# SUNRISE_EasyEDA.net
KiCad netlist of a schematic drawn in EasyEDA
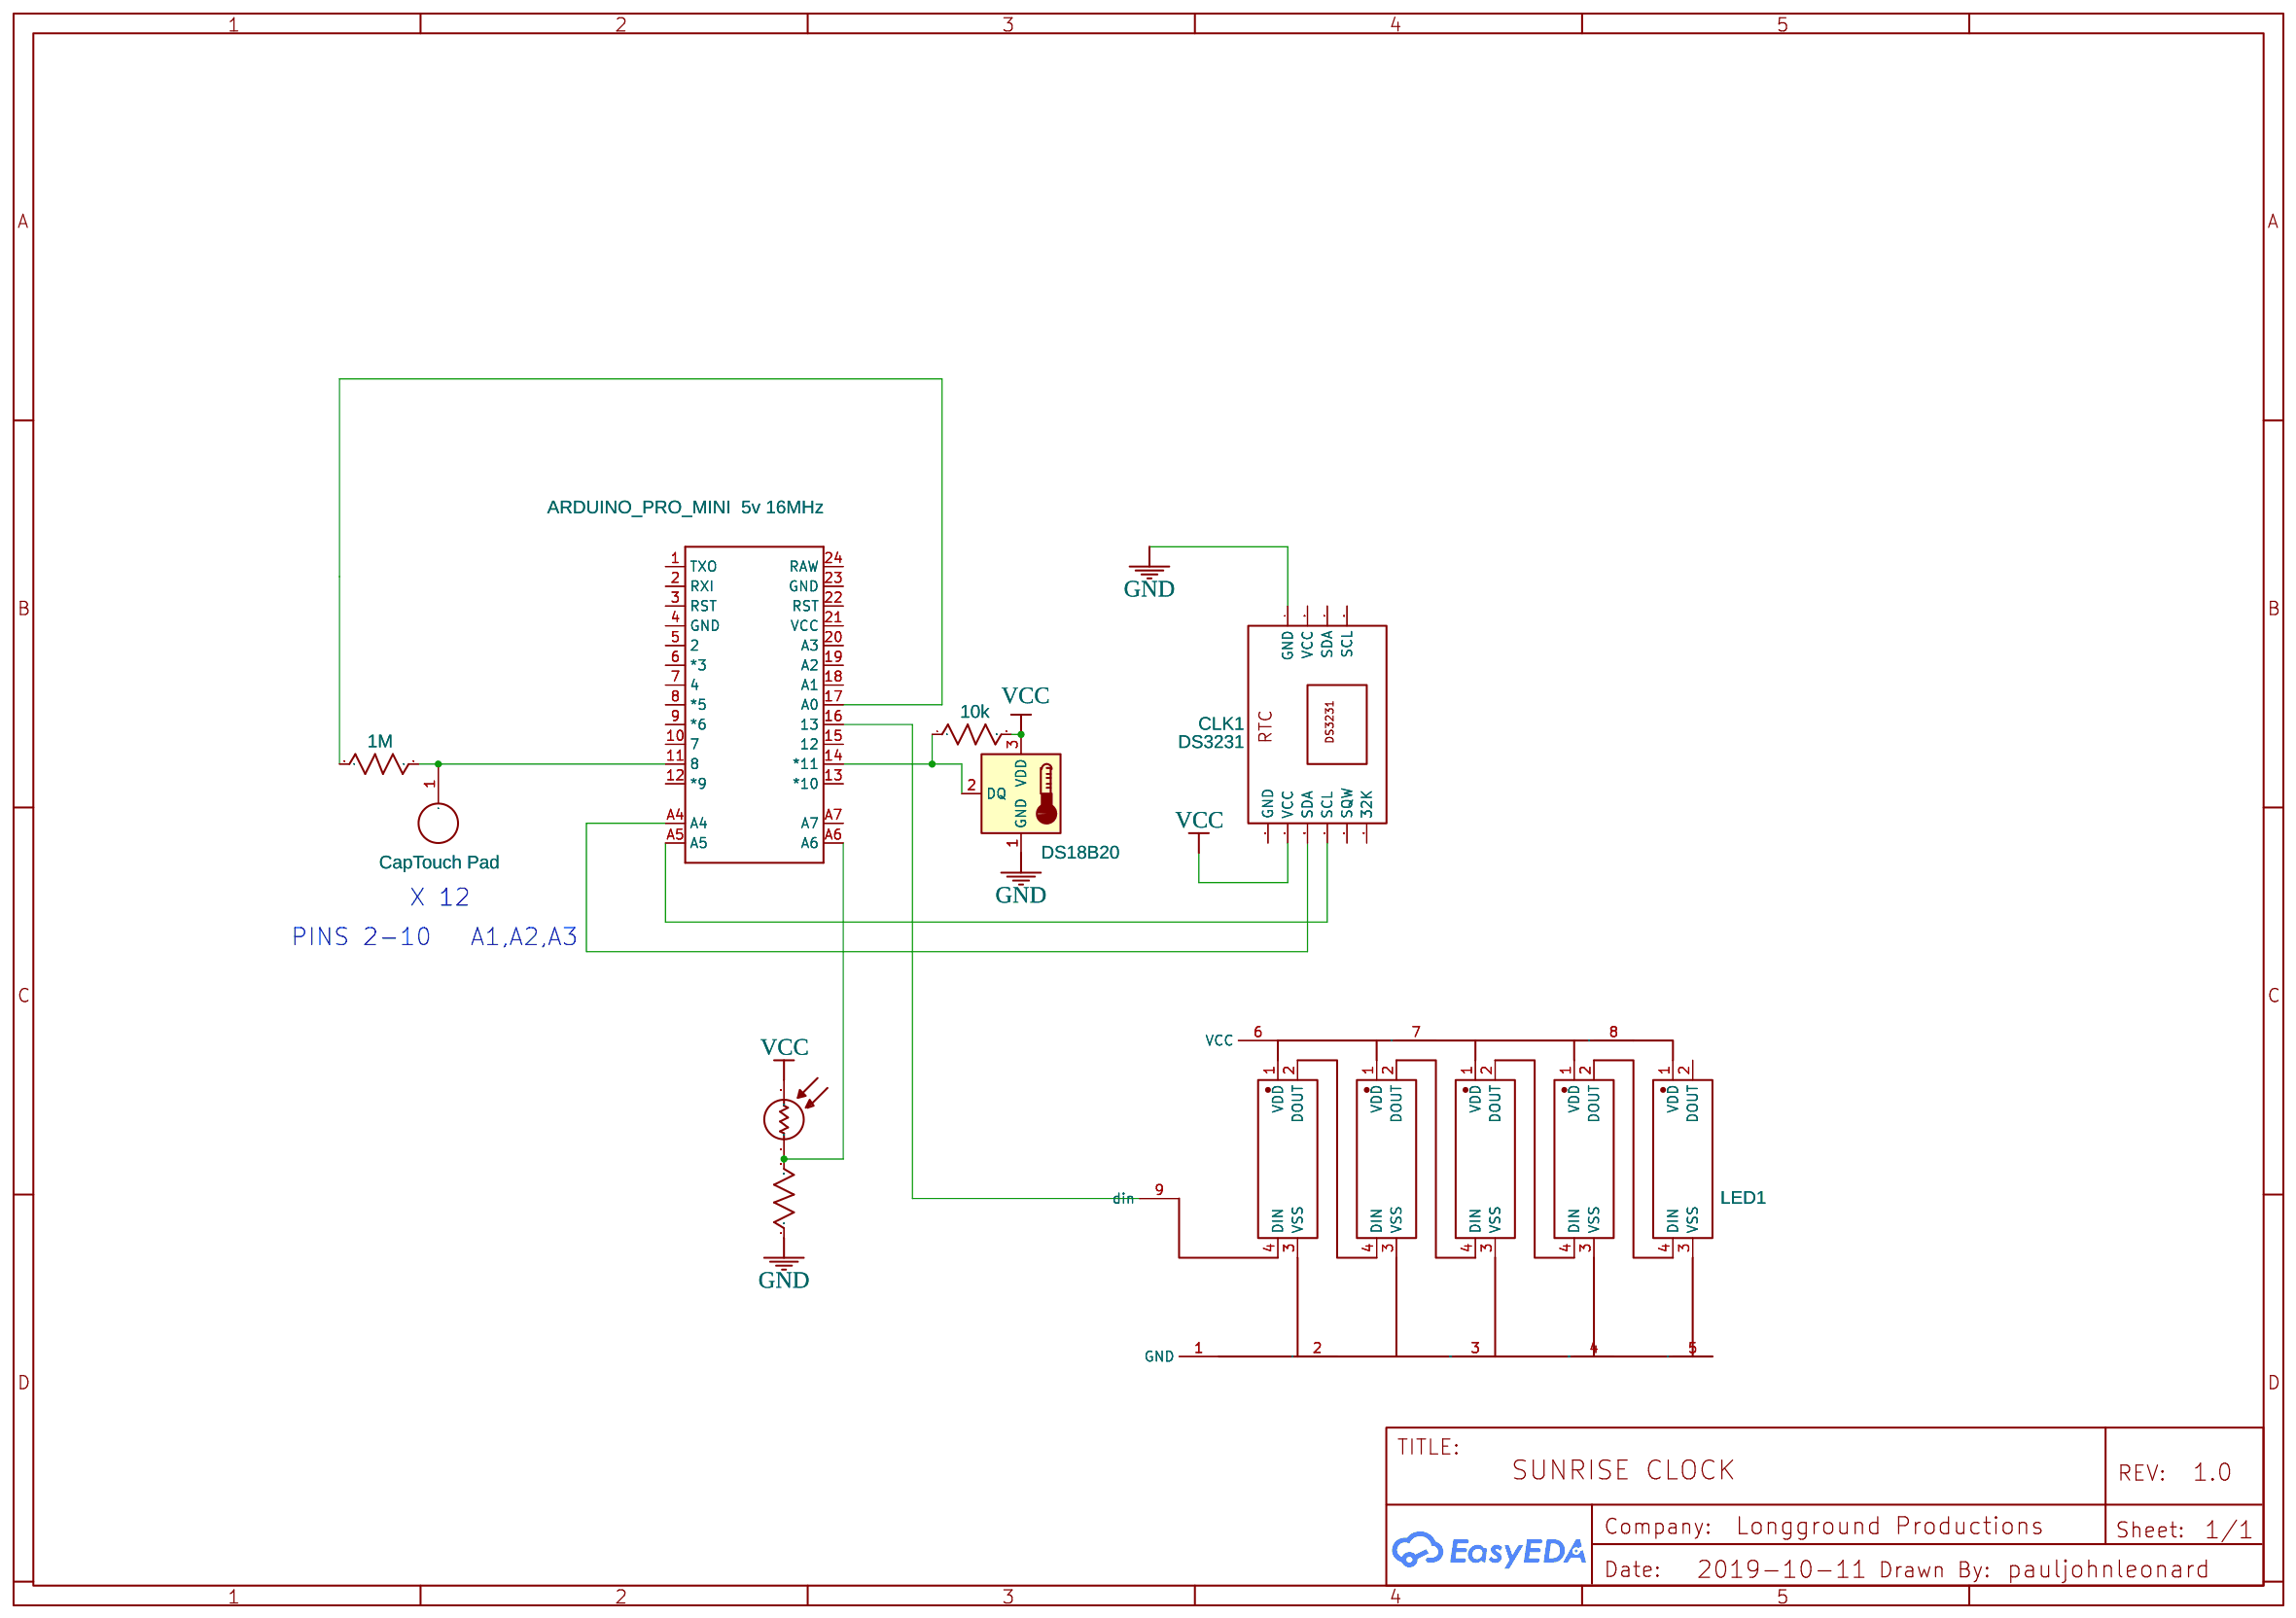
[diagram p0: schematic sheet]

(export (version "E")
  (design (tool "Eeschema 10.0.6"))
  (components
    (comp (ref "CLK1") (value "DS3231") (libsource (lib "") (part "Unknown_695_410")))
    (comp (ref "LDR1") (value "Photo-Resistor") (libsource (lib "") (part "Unknown_390_560")))
    (comp (ref "LED1")
      (value "схема коннектора для неопиксельного клинка,нижняя часть")
      (fields
        (field (name "BOM_Manufacturer Part") "WS2812B-3535")
        (field (name "BOM_Supplier Part") "C114583")
      )
      (libsource (lib "") (part "Unknown_840_690"))
    )
    (comp (ref "R1") (value "1M") (libsource (lib "") (part "Res_AXIAL-0.3(1/8W)_US")))
    (comp (ref "R2") (value "1k") (libsource (lib "") (part "Res_AXIAL-0.3(1/8W)_US_1")))
    (comp (ref "R3") (value "10k") (libsource (lib "") (part "Res_AXIAL-0.3(1/8W)_US")))
    (comp (ref "U1") (value "ARDUINO_PRO_MINI  5v 16MHz") (libsource (lib "") (part "Unknown_375_350")))
    (comp (ref "U2") (value "CapTouch Pad") (libsource (lib "") (part "Unknown_215_400")))
    (comp (ref "U3") (value "DS18B20") (libsource (lib "") (part "Unknown_505_395")))
  )
  (nets
    (net (code "1") (name "GND") (class "Default")
      (node (ref "CLK1") (pin "4") (pinfunction "GND_4") (pintype "passive"))
      (node (ref "R2") (pin "1") (pinfunction "1_1") (pintype "unspecified"))
      (node (ref "U3") (pin "1") (pinfunction "GND_1") (pintype "bidirectional"))
    )
    (net (code "2") (name "Net-(CLK1-SCL)_1") (class "Default")
      (node (ref "CLK1") (pin "11") (pinfunction "SCL_11") (pintype "unspecified"))
      (node (ref "U1") (pin "A5") (pinfunction "A5_A5") (pintype "unspecified"))
    )
    (net (code "3") (name "Net-(CLK1-SDA-Pad8)") (class "Default")
      (node (ref "CLK1") (pin "8") (pinfunction "SDA_8") (pintype "bidirectional"))
      (node (ref "U1") (pin "A4") (pinfunction "A4_A4") (pintype "unspecified"))
    )
    (net (code "4") (name "Net-(LDR1-2)") (class "Default")
      (node (ref "LDR1") (pin "2A") (pinfunction "2_2A") (pintype "unspecified"))
      (node (ref "R2") (pin "2") (pinfunction "2_2") (pintype "unspecified"))
      (node (ref "U1") (pin "A6") (pinfunction "A6_A6") (pintype "unspecified"))
    )
    (net (code "5") (name "Net-(U1-*11)") (class "Default")
      (node (ref "R3") (pin "1") (pinfunction "1_1") (pintype "unspecified"))
      (node (ref "U1") (pin "14") (pinfunction "*11_14") (pintype "unspecified"))
      (node (ref "U3") (pin "2") (pinfunction "DQ_2") (pintype "bidirectional"))
    )
    (net (code "6") (name "Net-(U1-8)") (class "Default")
      (node (ref "R1") (pin "2") (pinfunction "2_2") (pintype "unspecified"))
      (node (ref "U1") (pin "11") (pinfunction "8_11") (pintype "unspecified"))
      (node (ref "U2") (pin "1") (pinfunction "1_1") (pintype "unspecified"))
    )
    (net (code "7") (name "Net-(U1-A0)") (class "Default")
      (node (ref "R1") (pin "1") (pinfunction "1_1") (pintype "unspecified"))
      (node (ref "U1") (pin "17") (pinfunction "A0_17") (pintype "unspecified"))
    )
    (net (code "8") (name "VCC") (class "Default")
      (node (ref "CLK1") (pin "9") (pinfunction "VCC_9") (pintype "passive"))
      (node (ref "LDR1") (pin "1A") (pinfunction "1_1A") (pintype "unspecified"))
      (node (ref "R3") (pin "2") (pinfunction "2_2") (pintype "unspecified"))
      (node (ref "U3") (pin "3") (pinfunction "VDD_3") (pintype "bidirectional"))
    )
    (net (code "9") (name "unconnected-(CLK1-32K-Pad5)") (class "Default")
      (node (ref "CLK1") (pin "5") (pinfunction "32K_5") (pintype "input"))
    )
    (net (code "10") (name "unconnected-(CLK1-GND-Pad10)") (class "Default")
      (node (ref "CLK1") (pin "10") (pinfunction "GND_10") (pintype "passive"))
    )
    (net (code "11") (name "unconnected-(CLK1-SCL-Pad11)") (class "Default")
      (node (ref "CLK1") (pin "11") (pinfunction "SCL_11") (pintype "unspecified"))
    )
    (net (code "12") (name "unconnected-(CLK1-SDA-Pad2)") (class "Default")
      (node (ref "CLK1") (pin "2") (pinfunction "SDA_2") (pintype "bidirectional"))
    )
    (net (code "13") (name "unconnected-(CLK1-SQW-Pad5)") (class "Default")
      (node (ref "CLK1") (pin "5") (pinfunction "SQW_5") (pintype "input"))
    )
    (net (code "14") (name "unconnected-(CLK1-VCC-Pad3)") (class "Default")
      (node (ref "CLK1") (pin "3") (pinfunction "VCC_3") (pintype "passive"))
    )
    (net (code "15") (name "unconnected-(LED1-DIN-Pad4)") (class "Default")
      (node (ref "LED1") (pin "4") (pinfunction "DIN_4") (pintype "unspecified"))
    )
    (net (code "16") (name "unconnected-(LED1-DIN-Pad4)_1") (class "Default")
      (node (ref "LED1") (pin "4") (pinfunction "DIN_4") (pintype "unspecified"))
    )
    (net (code "17") (name "unconnected-(LED1-DIN-Pad4)_2") (class "Default")
      (node (ref "LED1") (pin "4") (pinfunction "DIN_4") (pintype "unspecified"))
    )
    (net (code "18") (name "unconnected-(LED1-DIN-Pad4)_3") (class "Default")
      (node (ref "LED1") (pin "4") (pinfunction "DIN_4") (pintype "unspecified"))
    )
    (net (code "19") (name "unconnected-(LED1-DIN-Pad4)_4") (class "Default")
      (node (ref "LED1") (pin "4") (pinfunction "DIN_4") (pintype "unspecified"))
    )
    (net (code "20") (name "unconnected-(LED1-DOUT-Pad2)") (class "Default")
      (node (ref "LED1") (pin "2") (pinfunction "DOUT_2") (pintype "unspecified"))
    )
    (net (code "21") (name "unconnected-(LED1-DOUT-Pad2)_1") (class "Default")
      (node (ref "LED1") (pin "2") (pinfunction "DOUT_2") (pintype "unspecified"))
    )
    (net (code "22") (name "unconnected-(LED1-DOUT-Pad2)_2") (class "Default")
      (node (ref "LED1") (pin "2") (pinfunction "DOUT_2") (pintype "unspecified"))
    )
    (net (code "23") (name "unconnected-(LED1-DOUT-Pad2)_3") (class "Default")
      (node (ref "LED1") (pin "2") (pinfunction "DOUT_2") (pintype "unspecified"))
    )
    (net (code "24") (name "unconnected-(LED1-DOUT-Pad2)_4") (class "Default")
      (node (ref "LED1") (pin "2") (pinfunction "DOUT_2") (pintype "unspecified"))
    )
    (net (code "25") (name "unconnected-(LED1-GND-Pad1)") (class "Default")
      (node (ref "LED1") (pin "1") (pinfunction "GND_1") (pintype "unspecified"))
    )
    (net (code "26") (name "unconnected-(LED1-GND-Pad2)") (class "Default")
      (node (ref "LED1") (pin "2") (pinfunction "GND_2") (pintype "unspecified"))
    )
    (net (code "27") (name "unconnected-(LED1-GND-Pad3)") (class "Default")
      (node (ref "LED1") (pin "3") (pinfunction "GND_3") (pintype "unspecified"))
    )
    (net (code "28") (name "unconnected-(LED1-GND-Pad4)") (class "Default")
      (node (ref "LED1") (pin "4") (pinfunction "GND_4") (pintype "unspecified"))
    )
    (net (code "29") (name "unconnected-(LED1-GND-Pad5)") (class "Default")
      (node (ref "LED1") (pin "5") (pinfunction "GND_5") (pintype "unspecified"))
    )
    (net (code "30") (name "unconnected-(LED1-VCC-Pad6)") (class "Default")
      (node (ref "LED1") (pin "6") (pinfunction "VCC_6") (pintype "unspecified"))
    )
    (net (code "31") (name "unconnected-(LED1-VDD-Pad1)") (class "Default")
      (node (ref "LED1") (pin "1") (pinfunction "VDD_1") (pintype "unspecified"))
    )
    (net (code "32") (name "unconnected-(LED1-VDD-Pad1)_1") (class "Default")
      (node (ref "LED1") (pin "1") (pinfunction "VDD_1") (pintype "unspecified"))
    )
    (net (code "33") (name "unconnected-(LED1-VDD-Pad1)_2") (class "Default")
      (node (ref "LED1") (pin "1") (pinfunction "VDD_1") (pintype "unspecified"))
    )
    (net (code "34") (name "unconnected-(LED1-VDD-Pad1)_3") (class "Default")
      (node (ref "LED1") (pin "1") (pinfunction "VDD_1") (pintype "unspecified"))
    )
    (net (code "35") (name "unconnected-(LED1-VDD-Pad1)_4") (class "Default")
      (node (ref "LED1") (pin "1") (pinfunction "VDD_1") (pintype "unspecified"))
    )
    (net (code "36") (name "unconnected-(LED1-VDD-Pad7)") (class "Default")
      (node (ref "LED1") (pin "7") (pinfunction "VDD_7") (pintype "unspecified"))
    )
    (net (code "37") (name "unconnected-(LED1-VDD-Pad8)") (class "Default")
      (node (ref "LED1") (pin "8") (pinfunction "VDD_8") (pintype "unspecified"))
    )
    (net (code "38") (name "unconnected-(LED1-VSS-Pad3)") (class "Default")
      (node (ref "LED1") (pin "3") (pinfunction "VSS_3") (pintype "unspecified"))
    )
    (net (code "39") (name "unconnected-(LED1-VSS-Pad3)_1") (class "Default")
      (node (ref "LED1") (pin "3") (pinfunction "VSS_3") (pintype "unspecified"))
    )
    (net (code "40") (name "unconnected-(LED1-VSS-Pad3)_2") (class "Default")
      (node (ref "LED1") (pin "3") (pinfunction "VSS_3") (pintype "unspecified"))
    )
    (net (code "41") (name "unconnected-(LED1-VSS-Pad3)_3") (class "Default")
      (node (ref "LED1") (pin "3") (pinfunction "VSS_3") (pintype "unspecified"))
    )
    (net (code "42") (name "unconnected-(LED1-VSS-Pad3)_4") (class "Default")
      (node (ref "LED1") (pin "3") (pinfunction "VSS_3") (pintype "unspecified"))
    )
    (net (code "43") (name "unconnected-(LED1-din-Pad9)") (class "Default")
      (node (ref "LED1") (pin "9") (pinfunction "din_9") (pintype "unspecified"))
    )
    (net (code "44") (name "unconnected-(U1-*3-Pad6)") (class "Default")
      (node (ref "U1") (pin "6") (pinfunction "*3_6") (pintype "unspecified"))
    )
    (net (code "45") (name "unconnected-(U1-*5-Pad8)") (class "Default")
      (node (ref "U1") (pin "8") (pinfunction "*5_8") (pintype "unspecified"))
    )
    (net (code "46") (name "unconnected-(U1-*6-Pad9)") (class "Default")
      (node (ref "U1") (pin "9") (pinfunction "*6_9") (pintype "unspecified"))
    )
    (net (code "47") (name "unconnected-(U1-*9-Pad12)") (class "Default")
      (node (ref "U1") (pin "12") (pinfunction "*9_12") (pintype "unspecified"))
    )
    (net (code "48") (name "unconnected-(U1-*10-Pad13)") (class "Default")
      (node (ref "U1") (pin "13") (pinfunction "*10_13") (pintype "unspecified"))
    )
    (net (code "49") (name "unconnected-(U1-2-Pad5)") (class "Default")
      (node (ref "U1") (pin "5") (pinfunction "2_5") (pintype "unspecified"))
    )
    (net (code "50") (name "unconnected-(U1-4-Pad7)") (class "Default")
      (node (ref "U1") (pin "7") (pinfunction "4_7") (pintype "unspecified"))
    )
    (net (code "51") (name "unconnected-(U1-7-Pad10)") (class "Default")
      (node (ref "U1") (pin "10") (pinfunction "7_10") (pintype "unspecified"))
    )
    (net (code "52") (name "unconnected-(U1-12-Pad15)") (class "Default")
      (node (ref "U1") (pin "15") (pinfunction "12_15") (pintype "unspecified"))
    )
    (net (code "53") (name "unconnected-(U1-13-Pad16)") (class "Default")
      (node (ref "U1") (pin "16") (pinfunction "13_16") (pintype "unspecified"))
    )
    (net (code "54") (name "unconnected-(U1-A1-Pad18)") (class "Default")
      (node (ref "U1") (pin "18") (pinfunction "A1_18") (pintype "unspecified"))
    )
    (net (code "55") (name "unconnected-(U1-A2-Pad19)") (class "Default")
      (node (ref "U1") (pin "19") (pinfunction "A2_19") (pintype "unspecified"))
    )
    (net (code "56") (name "unconnected-(U1-A3-Pad20)") (class "Default")
      (node (ref "U1") (pin "20") (pinfunction "A3_20") (pintype "unspecified"))
    )
    (net (code "57") (name "unconnected-(U1-GND-Pad4)") (class "Default")
      (node (ref "U1") (pin "4") (pinfunction "GND_4") (pintype "unspecified"))
    )
    (net (code "58") (name "unconnected-(U1-GND-Pad23)") (class "Default")
      (node (ref "U1") (pin "23") (pinfunction "GND_23") (pintype "unspecified"))
    )
    (net (code "59") (name "unconnected-(U1-PadA7)") (class "Default")
      (node (ref "U1") (pin "A7") (pinfunction "A7_A7") (pintype "unspecified"))
    )
    (net (code "60") (name "unconnected-(U1-RAW-Pad24)") (class "Default")
      (node (ref "U1") (pin "24") (pinfunction "RAW_24") (pintype "unspecified"))
    )
    (net (code "61") (name "unconnected-(U1-RST-Pad3)") (class "Default")
      (node (ref "U1") (pin "3") (pinfunction "RST_3") (pintype "unspecified"))
    )
    (net (code "62") (name "unconnected-(U1-RST-Pad22)") (class "Default")
      (node (ref "U1") (pin "22") (pinfunction "RST_22") (pintype "unspecified"))
    )
    (net (code "63") (name "unconnected-(U1-RXI-Pad2)") (class "Default")
      (node (ref "U1") (pin "2") (pinfunction "RXI_2") (pintype "unspecified"))
    )
    (net (code "64") (name "unconnected-(U1-TXO-Pad1)") (class "Default")
      (node (ref "U1") (pin "1") (pinfunction "TXO_1") (pintype "unspecified"))
    )
    (net (code "65") (name "unconnected-(U1-VCC-Pad21)") (class "Default")
      (node (ref "U1") (pin "21") (pinfunction "VCC_21") (pintype "unspecified"))
    )
  )
)
